# Sheet_QH.net
KiCad netlist of a schematic drawn in Altium Designer
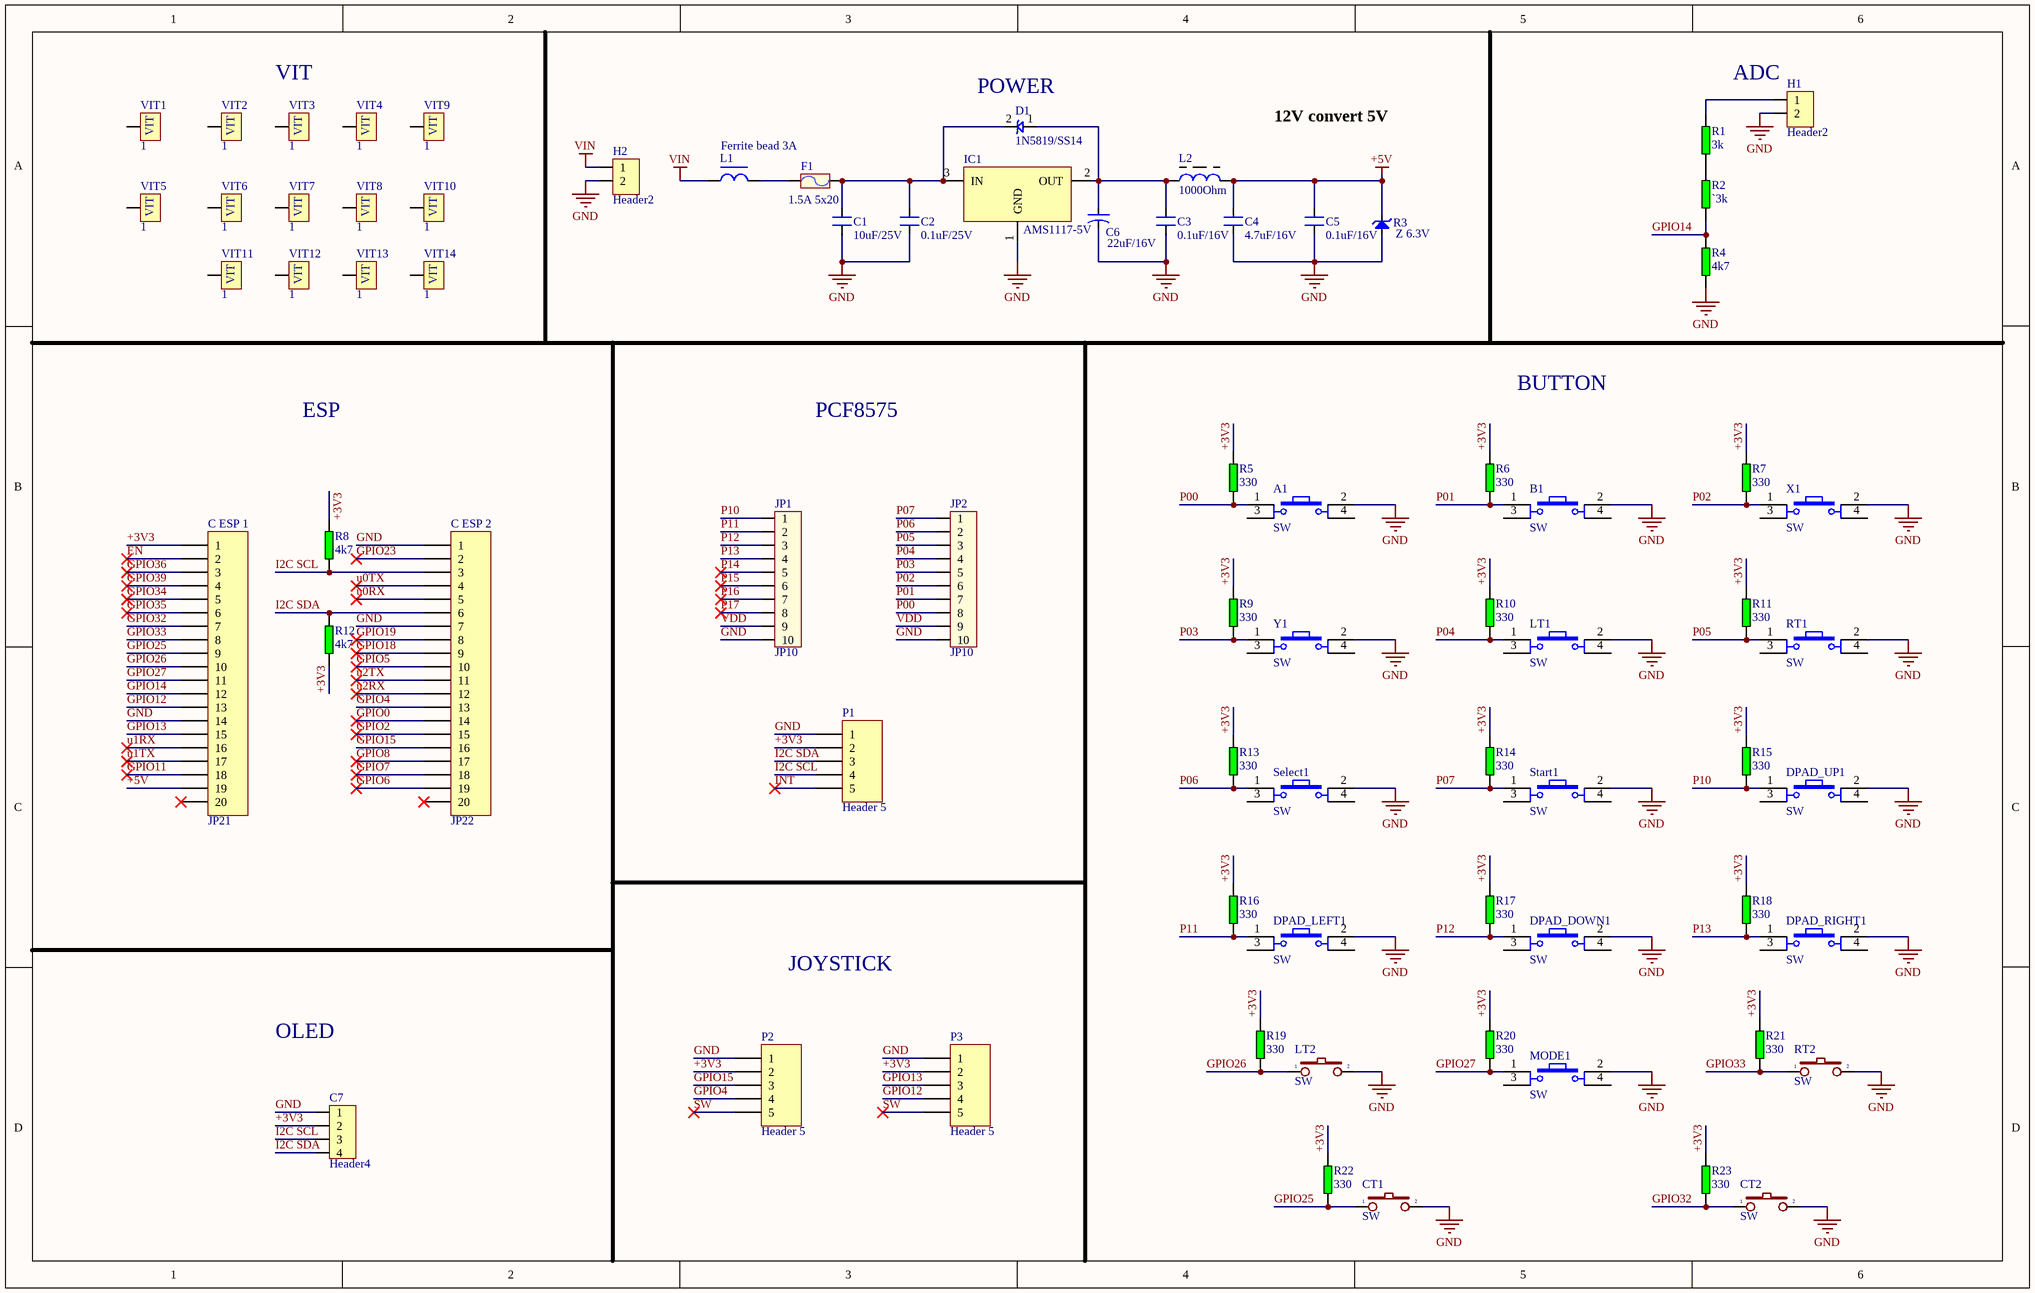
[diagram p0: Sheet_QH.SchDoc]

(export (version "E")
  (design (tool "Eeschema 10.0.6"))
  (components
    (comp (ref "A1")
      (value "SW")
      (footprint "SW4 - SMD")
      (description "Switch button 4 pin")
      (libsource (lib "My Library") (part "SW4"))
    )
    (comp (ref "B1")
      (value "SW")
      (footprint "SW4 - SMD")
      (description "Switch button 4 pin")
      (libsource (lib "My Library") (part "SW4"))
    )
    (comp (ref "C ESP 1")
      (value "JP21")
      (footprint "JP20-C1T")
      (description "WR-PHD 2.54 mm Angled Socket Header")
      (fields
        (field (name "MANUFACTURER") "Würth Elektronik eiSos GmbH")
        (field (name "PARTNO") "613020143121")
        (field (name "CREATED BY") "Karrer Zheng")
      )
      (libsource (lib "LIBRARY") (part "JP20"))
    )
    (comp (ref "C ESP 2")
      (value "JP22")
      (footprint "JP20-C1T")
      (description "WR-PHD 2.54 mm Angled Socket Header")
      (fields
        (field (name "MANUFACTURER") "Würth Elektronik eiSos GmbH")
        (field (name "PARTNO") "613020143121")
        (field (name "CREATED BY") "Karrer Zheng")
      )
      (libsource (lib "LIBRARY") (part "JP20"))
    )
    (comp (ref "C1") (value "10uF/25V") (footprint "CN-SMD-0805") (libsource (lib "LIBRARY") (part "CN")))
    (comp (ref "C2") (value "0.1uF/25V") (footprint "CN-SMD-0805") (libsource (lib "LIBRARY") (part "CN")))
    (comp (ref "C3") (value "0.1uF/16V") (footprint "CN-SMD-0805") (libsource (lib "LIBRARY") (part "CN")))
    (comp (ref "C4") (value "4.7uF/16V") (footprint "CN-SMD-0805") (libsource (lib "LIBRARY") (part "CN")))
    (comp (ref "C5") (value "0.1uF/16V") (footprint "CN-SMD-0805") (libsource (lib "LIBRARY") (part "CN")))
    (comp (ref "C6")
      (value "22uF/16V")
      (footprint "CAP-ALU-SMD-5.5x5.5")
      (description "Polarized Capacitor (Axial)")
      (fields (field (name "PUBLISHER") "Altium Limited"))
      (libsource (lib "LIBRARY") (part "CN-ALU-SMD"))
    )
    (comp (ref "C7")
      (value "Header4")
      (footprint "JP4-C1T")
      (description "Header IDC, 4 x 1 Pin Vertical 2.54mm Pitch (Non-Boxed, Male)")
      (fields
        (field (name "MANUFACTURER") "Würth Elektronik eiSos GmbH")
        (field (name "PARTNO") "613002143121")
        (field (name "CREATED BY") "Karrer Zheng")
      )
      (libsource (lib "My Library") (part "Header4"))
    )
    (comp (ref "CT1")
      (value "SW")
      (footprint "SW-SMD")
      (description "Switch button 2 pin")
      (libsource (lib "My Library") (part "SW2"))
    )
    (comp (ref "CT2")
      (value "SW")
      (footprint "SW-SMD")
      (description "Switch button 2 pin")
      (libsource (lib "My Library") (part "SW2"))
    )
    (comp (ref "D1")
      (value "1N5819/SS14")
      (footprint "SMA")
      (libsource (lib "LibraryMr_DH") (part "Diode Zener SMD"))
    )
    (comp (ref "DPAD_DOWN1")
      (value "SW")
      (footprint "SW4 - SMD")
      (description "Switch button 4 pin")
      (libsource (lib "My Library") (part "SW4"))
    )
    (comp (ref "DPAD_LEFT1")
      (value "SW")
      (footprint "SW4 - SMD")
      (description "Switch button 4 pin")
      (libsource (lib "My Library") (part "SW4"))
    )
    (comp (ref "DPAD_RIGHT1")
      (value "SW")
      (footprint "SW4 - SMD")
      (description "Switch button 4 pin")
      (libsource (lib "My Library") (part "SW4"))
    )
    (comp (ref "DPAD_UP1")
      (value "SW")
      (footprint "SW4 - SMD")
      (description "Switch button 4 pin")
      (libsource (lib "My Library") (part "SW4"))
    )
    (comp (ref "F1")
      (value "1.5A 5x20")
      (footprint "RES-SMD-1812")
      (description "Fuse")
      (fields (field (name "DESIGNED BY") "VanDungEvn"))
      (libsource (lib "LIBRARY") (part "Fuse"))
    )
    (comp (ref "H1")
      (value "Header2")
      (footprint "Header2")
      (description "Header IDC, 2 x 1 Pin Vertical 2.54mm Pitch (Non-Boxed, Male)")
      (fields
        (field (name "MANUFACTURER") "Würth Elektronik eiSos GmbH")
        (field (name "PARTNO") "613002143121")
        (field (name "CREATED BY") "Karrer Zheng")
      )
      (libsource (lib "LIBRARY") (part "Header2"))
    )
    (comp (ref "H2")
      (value "Header2")
      (footprint "KF2-3.5")
      (description "Header IDC, 2 x 1 Pin Vertical 2.54mm Pitch (Non-Boxed, Male)")
      (fields
        (field (name "MANUFACTURER") "Würth Elektronik eiSos GmbH")
        (field (name "PARTNO") "613002143121")
        (field (name "CREATED BY") "Karrer Zheng")
      )
      (libsource (lib "LIBRARY") (part "Header2"))
    )
    (comp (ref "IC1")
      (value "AMS1117-5V")
      (footprint "SOT223-4N")
      (description "800mA Low-Dropout Linear Regulator")
      (fields (field (name "CREATOR") "Nguyen Ba Bien"))
      (libsource (lib "LIBRARY") (part "LM1117"))
    )
    (comp (ref "JP1")
      (value "JP10")
      (footprint "JP10-C1T")
      (description "Connector 10")
      (libsource (lib "My Library") (part "Header10"))
    )
    (comp (ref "JP2")
      (value "JP10")
      (footprint "JP10-C1T")
      (description "Connector 10")
      (libsource (lib "My Library") (part "Header10"))
    )
    (comp (ref "L1")
      (value "Ferrite bead 3A")
      (footprint "L-DIP-M-6.0")
      (description "Inductor")
      (libsource (lib "LIBRARY") (part "L-DIP-1"))
    )
    (comp (ref "L2")
      (value "1000Ohm")
      (footprint "L-DIP-M-6.0")
      (description "Inductor")
      (libsource (lib "My Library") (part "Inductor Ferit"))
    )
    (comp (ref "LT1")
      (value "SW")
      (footprint "SW4 - SMD")
      (description "Switch button 4 pin")
      (libsource (lib "My Library") (part "SW4"))
    )
    (comp (ref "LT2")
      (value "SW")
      (footprint "SW-SMD")
      (description "Switch button 2 pin")
      (libsource (lib "My Library") (part "SW2"))
    )
    (comp (ref "MODE1")
      (value "SW")
      (footprint "SW4 - SMD")
      (description "Switch button 4 pin")
      (libsource (lib "My Library") (part "SW4"))
    )
    (comp (ref "P1")
      (value "Header 5")
      (footprint "JP5-C1T")
      (description "Header, 5-Pin")
      (fields (field (name "PUBLISHER") "Altium Limited"))
      (libsource (lib "My Library") (part "Header 5"))
    )
    (comp (ref "P2")
      (value "Header 5")
      (footprint "JP5-C1T")
      (description "Header, 5-Pin")
      (fields (field (name "PUBLISHER") "Altium Limited"))
      (libsource (lib "My Library") (part "Header 5"))
    )
    (comp (ref "P3")
      (value "Header 5")
      (footprint "JP5-C1T")
      (description "Header, 5-Pin")
      (fields (field (name "PUBLISHER") "Altium Limited"))
      (libsource (lib "My Library") (part "Header 5"))
    )
    (comp (ref "R1")
      (value "3k")
      (footprint "SM-0805")
      (description "Resistor 1/4W")
      (libsource (lib "My Library") (part "RES"))
    )
    (comp (ref "R2")
      (value "`3k")
      (footprint "SM-0805")
      (description "Resistor 1/4W")
      (libsource (lib "My Library") (part "RES"))
    )
    (comp (ref "R3")
      (value "Z 6.3V")
      (footprint "1N4148_SMD")
      (description "Zenner 4.8V")
      (libsource (lib "TechMT.VN_Lib_Project v2") (part "DIODE Zener"))
    )
    (comp (ref "R4")
      (value "4k7")
      (footprint "SM-0805")
      (description "Resistor 1/4W")
      (libsource (lib "My Library") (part "RES"))
    )
    (comp (ref "R5")
      (value "330")
      (footprint "SM-0805")
      (description "Resistor 1/4W")
      (libsource (lib "My Library") (part "RES"))
    )
    (comp (ref "R6")
      (value "330")
      (footprint "SM-0805")
      (description "Resistor 1/4W")
      (libsource (lib "My Library") (part "RES"))
    )
    (comp (ref "R7")
      (value "330")
      (footprint "SM-0805")
      (description "Resistor 1/4W")
      (libsource (lib "My Library") (part "RES"))
    )
    (comp (ref "R8")
      (value "4k7")
      (footprint "SM-0805")
      (description "Resistor 1/4W")
      (libsource (lib "My Library") (part "RES"))
    )
    (comp (ref "R9")
      (value "330")
      (footprint "SM-0805")
      (description "Resistor 1/4W")
      (libsource (lib "My Library") (part "RES"))
    )
    (comp (ref "R10")
      (value "330")
      (footprint "SM-0805")
      (description "Resistor 1/4W")
      (libsource (lib "My Library") (part "RES"))
    )
    (comp (ref "R11")
      (value "330")
      (footprint "SM-0805")
      (description "Resistor 1/4W")
      (libsource (lib "My Library") (part "RES"))
    )
    (comp (ref "R12")
      (value "4k7")
      (footprint "SM-0805")
      (description "Resistor 1/4W")
      (libsource (lib "My Library") (part "RES"))
    )
    (comp (ref "R13")
      (value "330")
      (footprint "SM-0805")
      (description "Resistor 1/4W")
      (libsource (lib "My Library") (part "RES"))
    )
    (comp (ref "R14")
      (value "330")
      (footprint "SM-0805")
      (description "Resistor 1/4W")
      (libsource (lib "My Library") (part "RES"))
    )
    (comp (ref "R15")
      (value "330")
      (footprint "SM-0805")
      (description "Resistor 1/4W")
      (libsource (lib "My Library") (part "RES"))
    )
    (comp (ref "R16")
      (value "330")
      (footprint "SM-0805")
      (description "Resistor 1/4W")
      (libsource (lib "My Library") (part "RES"))
    )
    (comp (ref "R17")
      (value "330")
      (footprint "SM-0805")
      (description "Resistor 1/4W")
      (libsource (lib "My Library") (part "RES"))
    )
    (comp (ref "R18")
      (value "330")
      (footprint "SM-0805")
      (description "Resistor 1/4W")
      (libsource (lib "My Library") (part "RES"))
    )
    (comp (ref "R19")
      (value "330")
      (footprint "SM-0805")
      (description "Resistor 1/4W")
      (libsource (lib "My Library") (part "RES"))
    )
    (comp (ref "R20")
      (value "330")
      (footprint "SM-0805")
      (description "Resistor 1/4W")
      (libsource (lib "My Library") (part "RES"))
    )
    (comp (ref "R21")
      (value "330")
      (footprint "SM-0805")
      (description "Resistor 1/4W")
      (libsource (lib "My Library") (part "RES"))
    )
    (comp (ref "R22")
      (value "330")
      (footprint "SM-0805")
      (description "Resistor 1/4W")
      (libsource (lib "My Library") (part "RES"))
    )
    (comp (ref "R23")
      (value "330")
      (footprint "SM-0805")
      (description "Resistor 1/4W")
      (libsource (lib "My Library") (part "RES"))
    )
    (comp (ref "RT1")
      (value "SW")
      (footprint "SW4 - SMD")
      (description "Switch button 4 pin")
      (libsource (lib "My Library") (part "SW4"))
    )
    (comp (ref "RT2")
      (value "SW")
      (footprint "SW-SMD")
      (description "Switch button 2 pin")
      (libsource (lib "My Library") (part "SW2"))
    )
    (comp (ref "Select1")
      (value "SW")
      (footprint "SW4 - SMD")
      (description "Switch button 4 pin")
      (libsource (lib "My Library") (part "SW4"))
    )
    (comp (ref "Start1")
      (value "SW")
      (footprint "SW4 - SMD")
      (description "Switch button 4 pin")
      (libsource (lib "My Library") (part "SW4"))
    )
    (comp (ref "VIT1")
      (value "1")
      (footprint "VIT")
      (description "Oc Vit")
      (libsource (lib "My Library") (part "VIT"))
    )
    (comp (ref "VIT2")
      (value "1")
      (footprint "VIT")
      (description "Oc Vit")
      (libsource (lib "My Library") (part "VIT"))
    )
    (comp (ref "VIT3")
      (value "1")
      (footprint "VIT")
      (description "Oc Vit")
      (libsource (lib "My Library") (part "VIT"))
    )
    (comp (ref "VIT4")
      (value "1")
      (footprint "VIT")
      (description "Oc Vit")
      (libsource (lib "My Library") (part "VIT"))
    )
    (comp (ref "VIT5")
      (value "1")
      (footprint "VIT")
      (description "Oc Vit")
      (libsource (lib "My Library") (part "VIT"))
    )
    (comp (ref "VIT6")
      (value "1")
      (footprint "VIT")
      (description "Oc Vit")
      (libsource (lib "My Library") (part "VIT"))
    )
    (comp (ref "VIT7")
      (value "1")
      (footprint "VIT")
      (description "Oc Vit")
      (libsource (lib "My Library") (part "VIT"))
    )
    (comp (ref "VIT8")
      (value "1")
      (footprint "VIT")
      (description "Oc Vit")
      (libsource (lib "My Library") (part "VIT"))
    )
    (comp (ref "VIT9")
      (value "1")
      (footprint "VIT")
      (description "Oc Vit")
      (libsource (lib "My Library") (part "VIT"))
    )
    (comp (ref "VIT10")
      (value "1")
      (footprint "VIT")
      (description "Oc Vit")
      (libsource (lib "My Library") (part "VIT"))
    )
    (comp (ref "VIT11")
      (value "1")
      (footprint "VIT")
      (description "Oc Vit")
      (libsource (lib "My Library") (part "VIT"))
    )
    (comp (ref "VIT12")
      (value "1")
      (footprint "VIT")
      (description "Oc Vit")
      (libsource (lib "My Library") (part "VIT"))
    )
    (comp (ref "VIT13")
      (value "1")
      (footprint "VIT")
      (description "Oc Vit")
      (libsource (lib "My Library") (part "VIT"))
    )
    (comp (ref "VIT14")
      (value "1")
      (footprint "VIT")
      (description "Oc Vit")
      (libsource (lib "My Library") (part "VIT"))
    )
    (comp (ref "X1")
      (value "SW")
      (footprint "SW4 - SMD")
      (description "Switch button 4 pin")
      (libsource (lib "My Library") (part "SW4"))
    )
    (comp (ref "Y1")
      (value "SW")
      (footprint "SW4 - SMD")
      (description "Switch button 4 pin")
      (libsource (lib "My Library") (part "SW4"))
    )
  )
  (nets
    (net (code "1") (name "+5V") (class "Default")
      (node (ref "C ESP 1") (pin "19") (pinfunction "19_19") (pintype "passive"))
      (node (ref "C4") (pin "2") (pinfunction "2_2") (pintype "passive"))
      (node (ref "C5") (pin "2") (pinfunction "2_2") (pintype "passive"))
      (node (ref "L2") (pin "2") (pinfunction "2_2") (pintype "passive"))
      (node (ref "R3") (pin "2") (pinfunction "K_2") (pintype "passive"))
    )
    (net (code "2") (name "/+3V3") (class "Default")
      (node (ref "C ESP 1") (pin "1") (pinfunction "1_1") (pintype "passive"))
      (node (ref "C7") (pin "2") (pinfunction "2_2") (pintype "passive"))
      (node (ref "P1") (pin "2") (pinfunction "2_2") (pintype "passive"))
      (node (ref "P2") (pin "2") (pinfunction "2_2") (pintype "passive"))
      (node (ref "P3") (pin "2") (pinfunction "2_2") (pintype "passive"))
      (node (ref "R10") (pin "2") (pinfunction "2_2") (pintype "passive"))
      (node (ref "R11") (pin "2") (pinfunction "2_2") (pintype "passive"))
      (node (ref "R12") (pin "1") (pinfunction "1_1") (pintype "passive"))
      (node (ref "R13") (pin "2") (pinfunction "2_2") (pintype "passive"))
      (node (ref "R14") (pin "2") (pinfunction "2_2") (pintype "passive"))
      (node (ref "R15") (pin "2") (pinfunction "2_2") (pintype "passive"))
      (node (ref "R16") (pin "2") (pinfunction "2_2") (pintype "passive"))
      (node (ref "R17") (pin "2") (pinfunction "2_2") (pintype "passive"))
      (node (ref "R18") (pin "2") (pinfunction "2_2") (pintype "passive"))
      (node (ref "R19") (pin "2") (pinfunction "2_2") (pintype "passive"))
      (node (ref "R20") (pin "2") (pinfunction "2_2") (pintype "passive"))
      (node (ref "R21") (pin "2") (pinfunction "2_2") (pintype "passive"))
      (node (ref "R22") (pin "2") (pinfunction "2_2") (pintype "passive"))
      (node (ref "R23") (pin "2") (pinfunction "2_2") (pintype "passive"))
      (node (ref "R5") (pin "2") (pinfunction "2_2") (pintype "passive"))
      (node (ref "R6") (pin "2") (pinfunction "2_2") (pintype "passive"))
      (node (ref "R7") (pin "2") (pinfunction "2_2") (pintype "passive"))
      (node (ref "R8") (pin "2") (pinfunction "2_2") (pintype "passive"))
      (node (ref "R9") (pin "2") (pinfunction "2_2") (pintype "passive"))
    )
    (net (code "3") (name "/EN") (class "Default")
      (node (ref "C ESP 1") (pin "2") (pinfunction "2_2") (pintype "passive+no_connect"))
    )
    (net (code "4") (name "/GPIO0") (class "Default")
      (node (ref "C ESP 2") (pin "14") (pinfunction "14_14") (pintype "passive+no_connect"))
    )
    (net (code "5") (name "/GPIO2") (class "Default")
      (node (ref "C ESP 2") (pin "15") (pinfunction "15_15") (pintype "passive+no_connect"))
    )
    (net (code "6") (name "/GPIO4") (class "Default")
      (node (ref "C ESP 2") (pin "13") (pinfunction "13_13") (pintype "passive"))
      (node (ref "P2") (pin "4") (pinfunction "4_4") (pintype "passive"))
    )
    (net (code "7") (name "/GPIO5") (class "Default")
      (node (ref "C ESP 2") (pin "10") (pinfunction "10_10") (pintype "passive+no_connect"))
    )
    (net (code "8") (name "/GPIO6") (class "Default")
      (node (ref "C ESP 2") (pin "19") (pinfunction "19_19") (pintype "passive+no_connect"))
    )
    (net (code "9") (name "/GPIO7") (class "Default")
      (node (ref "C ESP 2") (pin "18") (pinfunction "18_18") (pintype "passive+no_connect"))
    )
    (net (code "10") (name "/GPIO8") (class "Default")
      (node (ref "C ESP 2") (pin "17") (pinfunction "17_17") (pintype "passive+no_connect"))
    )
    (net (code "11") (name "/GPIO11") (class "Default")
      (node (ref "C ESP 1") (pin "18") (pinfunction "18_18") (pintype "passive+no_connect"))
    )
    (net (code "12") (name "/GPIO12") (class "Default")
      (node (ref "C ESP 1") (pin "13") (pinfunction "13_13") (pintype "passive"))
      (node (ref "P3") (pin "4") (pinfunction "4_4") (pintype "passive"))
    )
    (net (code "13") (name "/GPIO13") (class "Default")
      (node (ref "C ESP 1") (pin "15") (pinfunction "15_15") (pintype "passive"))
      (node (ref "P3") (pin "3") (pinfunction "3_3") (pintype "passive"))
    )
    (net (code "14") (name "/GPIO14") (class "Default")
      (node (ref "C ESP 1") (pin "12") (pinfunction "12_12") (pintype "passive"))
      (node (ref "R2") (pin "1") (pinfunction "1_1") (pintype "passive"))
      (node (ref "R4") (pin "2") (pinfunction "2_2") (pintype "passive"))
    )
    (net (code "15") (name "/GPIO15") (class "Default")
      (node (ref "C ESP 2") (pin "16") (pinfunction "16_16") (pintype "passive"))
      (node (ref "P2") (pin "3") (pinfunction "3_3") (pintype "passive"))
    )
    (net (code "16") (name "/GPIO18") (class "Default")
      (node (ref "C ESP 2") (pin "9") (pinfunction "9_9") (pintype "passive+no_connect"))
    )
    (net (code "17") (name "/GPIO19") (class "Default")
      (node (ref "C ESP 2") (pin "8") (pinfunction "8_8") (pintype "passive+no_connect"))
    )
    (net (code "18") (name "/GPIO23") (class "Default")
      (node (ref "C ESP 2") (pin "2") (pinfunction "2_2") (pintype "passive+no_connect"))
    )
    (net (code "19") (name "/GPIO25") (class "Default")
      (node (ref "C ESP 1") (pin "9") (pinfunction "9_9") (pintype "passive"))
      (node (ref "CT1") (pin "1") (pinfunction "1_1") (pintype "passive"))
      (node (ref "R22") (pin "1") (pinfunction "1_1") (pintype "passive"))
    )
    (net (code "20") (name "/GPIO26") (class "Default")
      (node (ref "C ESP 1") (pin "10") (pinfunction "10_10") (pintype "passive"))
      (node (ref "LT2") (pin "1") (pinfunction "1_1") (pintype "passive"))
      (node (ref "R19") (pin "1") (pinfunction "1_1") (pintype "passive"))
    )
    (net (code "21") (name "/GPIO27") (class "Default")
      (node (ref "C ESP 1") (pin "11") (pinfunction "11_11") (pintype "passive"))
      (node (ref "MODE1") (pin "1") (pintype "passive"))
      (node (ref "R20") (pin "1") (pinfunction "1_1") (pintype "passive"))
    )
    (net (code "22") (name "/GPIO32") (class "Default")
      (node (ref "C ESP 1") (pin "7") (pinfunction "7_7") (pintype "passive"))
      (node (ref "CT2") (pin "1") (pinfunction "1_1") (pintype "passive"))
      (node (ref "R23") (pin "1") (pinfunction "1_1") (pintype "passive"))
    )
    (net (code "23") (name "/GPIO33") (class "Default")
      (node (ref "C ESP 1") (pin "8") (pinfunction "8_8") (pintype "passive"))
      (node (ref "R21") (pin "1") (pinfunction "1_1") (pintype "passive"))
      (node (ref "RT2") (pin "1") (pinfunction "1_1") (pintype "passive"))
    )
    (net (code "24") (name "/GPIO34") (class "Default")
      (node (ref "C ESP 1") (pin "5") (pinfunction "5_5") (pintype "passive+no_connect"))
    )
    (net (code "25") (name "/GPIO35") (class "Default")
      (node (ref "C ESP 1") (pin "6") (pinfunction "6_6") (pintype "passive+no_connect"))
    )
    (net (code "26") (name "/GPIO36") (class "Default")
      (node (ref "C ESP 1") (pin "3") (pinfunction "3_3") (pintype "passive+no_connect"))
    )
    (net (code "27") (name "/GPIO39") (class "Default")
      (node (ref "C ESP 1") (pin "4") (pinfunction "4_4") (pintype "passive+no_connect"))
    )
    (net (code "28") (name "/I2C SCL") (class "Default")
      (node (ref "C ESP 2") (pin "3") (pinfunction "3_3") (pintype "passive"))
      (node (ref "C7") (pin "3") (pinfunction "3_3") (pintype "passive"))
      (node (ref "P1") (pin "4") (pinfunction "4_4") (pintype "passive"))
      (node (ref "R8") (pin "1") (pinfunction "1_1") (pintype "passive"))
    )
    (net (code "29") (name "/I2C SDA") (class "Default")
      (node (ref "C ESP 2") (pin "6") (pinfunction "6_6") (pintype "passive"))
      (node (ref "C7") (pin "4") (pinfunction "4_4") (pintype "passive"))
      (node (ref "P1") (pin "3") (pinfunction "3_3") (pintype "passive"))
      (node (ref "R12") (pin "2") (pinfunction "2_2") (pintype "passive"))
    )
    (net (code "30") (name "/INT") (class "Default")
      (node (ref "P1") (pin "5") (pinfunction "5_5") (pintype "passive+no_connect"))
    )
    (net (code "31") (name "/P00") (class "Default")
      (node (ref "A1") (pin "1") (pintype "passive"))
      (node (ref "JP2") (pin "8") (pinfunction "8_8") (pintype "passive"))
      (node (ref "R5") (pin "1") (pinfunction "1_1") (pintype "passive"))
    )
    (net (code "32") (name "/P01") (class "Default")
      (node (ref "B1") (pin "1") (pintype "passive"))
      (node (ref "JP2") (pin "7") (pinfunction "7_7") (pintype "passive"))
      (node (ref "R6") (pin "1") (pinfunction "1_1") (pintype "passive"))
    )
    (net (code "33") (name "/P02") (class "Default")
      (node (ref "JP2") (pin "6") (pinfunction "6_6") (pintype "passive"))
      (node (ref "R7") (pin "1") (pinfunction "1_1") (pintype "passive"))
      (node (ref "X1") (pin "1") (pintype "passive"))
    )
    (net (code "34") (name "/P03") (class "Default")
      (node (ref "JP2") (pin "5") (pinfunction "5_5") (pintype "passive"))
      (node (ref "R9") (pin "1") (pinfunction "1_1") (pintype "passive"))
      (node (ref "Y1") (pin "1") (pintype "passive"))
    )
    (net (code "35") (name "/P04") (class "Default")
      (node (ref "JP2") (pin "4") (pinfunction "4_4") (pintype "passive"))
      (node (ref "LT1") (pin "1") (pintype "passive"))
      (node (ref "R10") (pin "1") (pinfunction "1_1") (pintype "passive"))
    )
    (net (code "36") (name "/P05") (class "Default")
      (node (ref "JP2") (pin "3") (pinfunction "3_3") (pintype "passive"))
      (node (ref "R11") (pin "1") (pinfunction "1_1") (pintype "passive"))
      (node (ref "RT1") (pin "1") (pintype "passive"))
    )
    (net (code "37") (name "/P06") (class "Default")
      (node (ref "JP2") (pin "2") (pinfunction "2_2") (pintype "passive"))
      (node (ref "R13") (pin "1") (pinfunction "1_1") (pintype "passive"))
      (node (ref "Select1") (pin "1") (pintype "passive"))
    )
    (net (code "38") (name "/P07") (class "Default")
      (node (ref "JP2") (pin "1") (pinfunction "1_1") (pintype "passive"))
      (node (ref "R14") (pin "1") (pinfunction "1_1") (pintype "passive"))
      (node (ref "Start1") (pin "1") (pintype "passive"))
    )
    (net (code "39") (name "/P10") (class "Default")
      (node (ref "DPAD_UP1") (pin "1") (pintype "passive"))
      (node (ref "JP1") (pin "1") (pinfunction "1_1") (pintype "passive"))
      (node (ref "R15") (pin "1") (pinfunction "1_1") (pintype "passive"))
    )
    (net (code "40") (name "/P11") (class "Default")
      (node (ref "DPAD_LEFT1") (pin "1") (pintype "passive"))
      (node (ref "JP1") (pin "2") (pinfunction "2_2") (pintype "passive"))
      (node (ref "R16") (pin "1") (pinfunction "1_1") (pintype "passive"))
    )
    (net (code "41") (name "/P12") (class "Default")
      (node (ref "DPAD_DOWN1") (pin "1") (pintype "passive"))
      (node (ref "JP1") (pin "3") (pinfunction "3_3") (pintype "passive"))
      (node (ref "R17") (pin "1") (pinfunction "1_1") (pintype "passive"))
    )
    (net (code "42") (name "/P13") (class "Default")
      (node (ref "DPAD_RIGHT1") (pin "1") (pintype "passive"))
      (node (ref "JP1") (pin "4") (pinfunction "4_4") (pintype "passive"))
      (node (ref "R18") (pin "1") (pinfunction "1_1") (pintype "passive"))
    )
    (net (code "43") (name "/P14") (class "Default")
      (node (ref "JP1") (pin "5") (pinfunction "5_5") (pintype "passive+no_connect"))
    )
    (net (code "44") (name "/P15") (class "Default")
      (node (ref "JP1") (pin "6") (pinfunction "6_6") (pintype "passive+no_connect"))
    )
    (net (code "45") (name "/P16") (class "Default")
      (node (ref "JP1") (pin "7") (pinfunction "7_7") (pintype "passive+no_connect"))
    )
    (net (code "46") (name "/P17") (class "Default")
      (node (ref "JP1") (pin "8") (pinfunction "8_8") (pintype "passive+no_connect"))
    )
    (net (code "47") (name "/SW") (class "Default")
      (node (ref "P2") (pin "5") (pinfunction "5_5") (pintype "passive"))
      (node (ref "P3") (pin "5") (pinfunction "5_5") (pintype "passive"))
    )
    (net (code "48") (name "/VDD") (class "Default")
      (node (ref "JP1") (pin "9") (pinfunction "9_9") (pintype "passive"))
      (node (ref "JP2") (pin "9") (pinfunction "9_9") (pintype "passive"))
    )
    (net (code "49") (name "/u0RX") (class "Default")
      (node (ref "C ESP 2") (pin "5") (pinfunction "5_5") (pintype "passive+no_connect"))
    )
    (net (code "50") (name "/u0TX") (class "Default")
      (node (ref "C ESP 2") (pin "4") (pinfunction "4_4") (pintype "passive+no_connect"))
    )
    (net (code "51") (name "/u1RX") (class "Default")
      (node (ref "C ESP 1") (pin "16") (pinfunction "16_16") (pintype "passive+no_connect"))
    )
    (net (code "52") (name "/u1TX") (class "Default")
      (node (ref "C ESP 1") (pin "17") (pinfunction "17_17") (pintype "passive+no_connect"))
    )
    (net (code "53") (name "/u2RX") (class "Default")
      (node (ref "C ESP 2") (pin "12") (pinfunction "12_12") (pintype "passive+no_connect"))
    )
    (net (code "54") (name "/u2TX") (class "Default")
      (node (ref "C ESP 2") (pin "11") (pinfunction "11_11") (pintype "passive+no_connect"))
    )
    (net (code "55") (name "GND") (class "Default")
      (node (ref "A1") (pin "2") (pintype "passive"))
      (node (ref "B1") (pin "2") (pintype "passive"))
      (node (ref "C ESP 1") (pin "14") (pinfunction "14_14") (pintype "passive"))
      (node (ref "C ESP 2") (pin "1") (pinfunction "1_1") (pintype "passive"))
      (node (ref "C ESP 2") (pin "7") (pinfunction "7_7") (pintype "passive"))
      (node (ref "C1") (pin "1") (pinfunction "1_1") (pintype "passive"))
      (node (ref "C2") (pin "1") (pinfunction "1_1") (pintype "passive"))
      (node (ref "C3") (pin "1") (pinfunction "1_1") (pintype "passive"))
      (node (ref "C4") (pin "1") (pinfunction "1_1") (pintype "passive"))
      (node (ref "C5") (pin "1") (pinfunction "1_1") (pintype "passive"))
      (node (ref "C6") (pin "2") (pinfunction "2_2") (pintype "passive"))
      (node (ref "C7") (pin "1") (pinfunction "1_1") (pintype "passive"))
      (node (ref "CT1") (pin "2") (pinfunction "2_2") (pintype "passive"))
      (node (ref "CT2") (pin "2") (pinfunction "2_2") (pintype "passive"))
      (node (ref "DPAD_DOWN1") (pin "2") (pintype "passive"))
      (node (ref "DPAD_LEFT1") (pin "2") (pintype "passive"))
      (node (ref "DPAD_RIGHT1") (pin "2") (pintype "passive"))
      (node (ref "DPAD_UP1") (pin "2") (pintype "passive"))
      (node (ref "H1") (pin "2") (pinfunction "2_2") (pintype "passive"))
      (node (ref "H2") (pin "2") (pinfunction "2_2") (pintype "passive"))
      (node (ref "IC1") (pin "1") (pinfunction "GND_1") (pintype "passive"))
      (node (ref "JP1") (pin "10") (pinfunction "10_10") (pintype "passive"))
      (node (ref "JP2") (pin "10") (pinfunction "10_10") (pintype "passive"))
      (node (ref "LT1") (pin "2") (pintype "passive"))
      (node (ref "LT2") (pin "2") (pinfunction "2_2") (pintype "passive"))
      (node (ref "MODE1") (pin "2") (pintype "passive"))
      (node (ref "P1") (pin "1") (pinfunction "1_1") (pintype "passive"))
      (node (ref "P2") (pin "1") (pinfunction "1_1") (pintype "passive"))
      (node (ref "P3") (pin "1") (pinfunction "1_1") (pintype "passive"))
      (node (ref "R3") (pin "1") (pinfunction "A_1") (pintype "passive"))
      (node (ref "R4") (pin "1") (pinfunction "1_1") (pintype "passive"))
      (node (ref "RT1") (pin "2") (pintype "passive"))
      (node (ref "RT2") (pin "2") (pinfunction "2_2") (pintype "passive"))
      (node (ref "Select1") (pin "2") (pintype "passive"))
      (node (ref "Start1") (pin "2") (pintype "passive"))
      (node (ref "X1") (pin "2") (pintype "passive"))
      (node (ref "Y1") (pin "2") (pintype "passive"))
    )
    (net (code "56") (name "Net-(F1-Pad1)") (class "Default")
      (node (ref "F1") (pin "1") (pinfunction "1_1") (pintype "passive"))
      (node (ref "L1") (pin "2") (pinfunction "2_2") (pintype "passive"))
    )
    (net (code "57") (name "Net-(H1-Pad1)") (class "Default")
      (node (ref "H1") (pin "1") (pinfunction "1_1") (pintype "passive"))
      (node (ref "R1") (pin "2") (pinfunction "2_2") (pintype "passive"))
    )
    (net (code "58") (name "Net-(IC1-IN)") (class "Default")
      (node (ref "C1") (pin "2") (pinfunction "2_2") (pintype "passive"))
      (node (ref "C2") (pin "2") (pinfunction "2_2") (pintype "passive"))
      (node (ref "D1") (pin "2") (pinfunction "2_2") (pintype "passive"))
      (node (ref "F1") (pin "2") (pinfunction "2_2") (pintype "passive"))
      (node (ref "IC1") (pin "3") (pinfunction "IN_3") (pintype "passive"))
    )
    (net (code "59") (name "Net-(IC1-OUT)") (class "Default")
      (node (ref "C3") (pin "2") (pinfunction "2_2") (pintype "passive"))
      (node (ref "C6") (pin "1") (pinfunction "1_1") (pintype "passive"))
      (node (ref "D1") (pin "1") (pinfunction "1_1") (pintype "passive"))
      (node (ref "IC1") (pin "2") (pinfunction "OUT_2") (pintype "passive"))
      (node (ref "L2") (pin "1") (pinfunction "1_1") (pintype "passive"))
    )
    (net (code "60") (name "Net-(R1-Pad1)") (class "Default")
      (node (ref "R1") (pin "1") (pinfunction "1_1") (pintype "passive"))
      (node (ref "R2") (pin "2") (pinfunction "2_2") (pintype "passive"))
    )
    (net (code "61") (name "VIN") (class "Default")
      (node (ref "H2") (pin "1") (pinfunction "1_1") (pintype "passive"))
      (node (ref "L1") (pin "1") (pinfunction "1_1") (pintype "passive"))
    )
    (net (code "62") (name "unconnected-(A1-Pad3)") (class "Default")
      (node (ref "A1") (pin "3") (pintype "passive"))
    )
    (net (code "63") (name "unconnected-(A1-Pad4)") (class "Default")
      (node (ref "A1") (pin "4") (pintype "passive"))
    )
    (net (code "64") (name "unconnected-(B1-Pad3)") (class "Default")
      (node (ref "B1") (pin "3") (pintype "passive"))
    )
    (net (code "65") (name "unconnected-(B1-Pad4)") (class "Default")
      (node (ref "B1") (pin "4") (pintype "passive"))
    )
    (net (code "66") (name "unconnected-(C ESP 1-Pad20)") (class "Default")
      (node (ref "C ESP 1") (pin "20") (pinfunction "20_20") (pintype "passive+no_connect"))
    )
    (net (code "67") (name "unconnected-(C ESP 2-Pad20)") (class "Default")
      (node (ref "C ESP 2") (pin "20") (pinfunction "20_20") (pintype "passive+no_connect"))
    )
    (net (code "68") (name "unconnected-(DPAD_DOWN1-Pad3)") (class "Default")
      (node (ref "DPAD_DOWN1") (pin "3") (pintype "passive"))
    )
    (net (code "69") (name "unconnected-(DPAD_DOWN1-Pad4)") (class "Default")
      (node (ref "DPAD_DOWN1") (pin "4") (pintype "passive"))
    )
    (net (code "70") (name "unconnected-(DPAD_LEFT1-Pad3)") (class "Default")
      (node (ref "DPAD_LEFT1") (pin "3") (pintype "passive"))
    )
    (net (code "71") (name "unconnected-(DPAD_LEFT1-Pad4)") (class "Default")
      (node (ref "DPAD_LEFT1") (pin "4") (pintype "passive"))
    )
    (net (code "72") (name "unconnected-(DPAD_RIGHT1-Pad3)") (class "Default")
      (node (ref "DPAD_RIGHT1") (pin "3") (pintype "passive"))
    )
    (net (code "73") (name "unconnected-(DPAD_RIGHT1-Pad4)") (class "Default")
      (node (ref "DPAD_RIGHT1") (pin "4") (pintype "passive"))
    )
    (net (code "74") (name "unconnected-(DPAD_UP1-Pad3)") (class "Default")
      (node (ref "DPAD_UP1") (pin "3") (pintype "passive"))
    )
    (net (code "75") (name "unconnected-(DPAD_UP1-Pad4)") (class "Default")
      (node (ref "DPAD_UP1") (pin "4") (pintype "passive"))
    )
    (net (code "76") (name "unconnected-(LT1-Pad3)") (class "Default")
      (node (ref "LT1") (pin "3") (pintype "passive"))
    )
    (net (code "77") (name "unconnected-(LT1-Pad4)") (class "Default")
      (node (ref "LT1") (pin "4") (pintype "passive"))
    )
    (net (code "78") (name "unconnected-(MODE1-Pad3)") (class "Default")
      (node (ref "MODE1") (pin "3") (pintype "passive"))
    )
    (net (code "79") (name "unconnected-(MODE1-Pad4)") (class "Default")
      (node (ref "MODE1") (pin "4") (pintype "passive"))
    )
    (net (code "80") (name "unconnected-(RT1-Pad3)") (class "Default")
      (node (ref "RT1") (pin "3") (pintype "passive"))
    )
    (net (code "81") (name "unconnected-(RT1-Pad4)") (class "Default")
      (node (ref "RT1") (pin "4") (pintype "passive"))
    )
    (net (code "82") (name "unconnected-(Select1-Pad3)") (class "Default")
      (node (ref "Select1") (pin "3") (pintype "passive"))
    )
    (net (code "83") (name "unconnected-(Select1-Pad4)") (class "Default")
      (node (ref "Select1") (pin "4") (pintype "passive"))
    )
    (net (code "84") (name "unconnected-(Start1-Pad3)") (class "Default")
      (node (ref "Start1") (pin "3") (pintype "passive"))
    )
    (net (code "85") (name "unconnected-(Start1-Pad4)") (class "Default")
      (node (ref "Start1") (pin "4") (pintype "passive"))
    )
    (net (code "86") (name "unconnected-(VIT1-1-PadVIT1)") (class "Default")
      (node (ref "VIT1") (pin "VIT1") (pinfunction "1_VIT1") (pintype "passive"))
    )
    (net (code "87") (name "unconnected-(VIT2-1-PadVIT1)") (class "Default")
      (node (ref "VIT2") (pin "VIT1") (pinfunction "1_VIT1") (pintype "passive"))
    )
    (net (code "88") (name "unconnected-(VIT3-1-PadVIT1)") (class "Default")
      (node (ref "VIT3") (pin "VIT1") (pinfunction "1_VIT1") (pintype "passive"))
    )
    (net (code "89") (name "unconnected-(VIT4-1-PadVIT1)") (class "Default")
      (node (ref "VIT4") (pin "VIT1") (pinfunction "1_VIT1") (pintype "passive"))
    )
    (net (code "90") (name "unconnected-(VIT5-1-PadVIT1)") (class "Default")
      (node (ref "VIT5") (pin "VIT1") (pinfunction "1_VIT1") (pintype "passive"))
    )
    (net (code "91") (name "unconnected-(VIT6-1-PadVIT1)") (class "Default")
      (node (ref "VIT6") (pin "VIT1") (pinfunction "1_VIT1") (pintype "passive"))
    )
    (net (code "92") (name "unconnected-(VIT7-1-PadVIT1)") (class "Default")
      (node (ref "VIT7") (pin "VIT1") (pinfunction "1_VIT1") (pintype "passive"))
    )
    (net (code "93") (name "unconnected-(VIT8-1-PadVIT1)") (class "Default")
      (node (ref "VIT8") (pin "VIT1") (pinfunction "1_VIT1") (pintype "passive"))
    )
    (net (code "94") (name "unconnected-(VIT9-1-PadVIT1)") (class "Default")
      (node (ref "VIT9") (pin "VIT1") (pinfunction "1_VIT1") (pintype "passive"))
    )
    (net (code "95") (name "unconnected-(VIT10-1-PadVIT1)") (class "Default")
      (node (ref "VIT10") (pin "VIT1") (pinfunction "1_VIT1") (pintype "passive"))
    )
    (net (code "96") (name "unconnected-(VIT11-1-PadVIT1)") (class "Default")
      (node (ref "VIT11") (pin "VIT1") (pinfunction "1_VIT1") (pintype "passive"))
    )
    (net (code "97") (name "unconnected-(VIT12-1-PadVIT1)") (class "Default")
      (node (ref "VIT12") (pin "VIT1") (pinfunction "1_VIT1") (pintype "passive"))
    )
    (net (code "98") (name "unconnected-(VIT13-1-PadVIT1)") (class "Default")
      (node (ref "VIT13") (pin "VIT1") (pinfunction "1_VIT1") (pintype "passive"))
    )
    (net (code "99") (name "unconnected-(VIT14-1-PadVIT1)") (class "Default")
      (node (ref "VIT14") (pin "VIT1") (pinfunction "1_VIT1") (pintype "passive"))
    )
    (net (code "100") (name "unconnected-(X1-Pad3)") (class "Default")
      (node (ref "X1") (pin "3") (pintype "passive"))
    )
    (net (code "101") (name "unconnected-(X1-Pad4)") (class "Default")
      (node (ref "X1") (pin "4") (pintype "passive"))
    )
    (net (code "102") (name "unconnected-(Y1-Pad3)") (class "Default")
      (node (ref "Y1") (pin "3") (pintype "passive"))
    )
    (net (code "103") (name "unconnected-(Y1-Pad4)") (class "Default")
      (node (ref "Y1") (pin "4") (pintype "passive"))
    )
  )
)
